# MiP_ProMini_16MHz-Pack.net
KiCad netlist of a schematic drawn in EAGLE
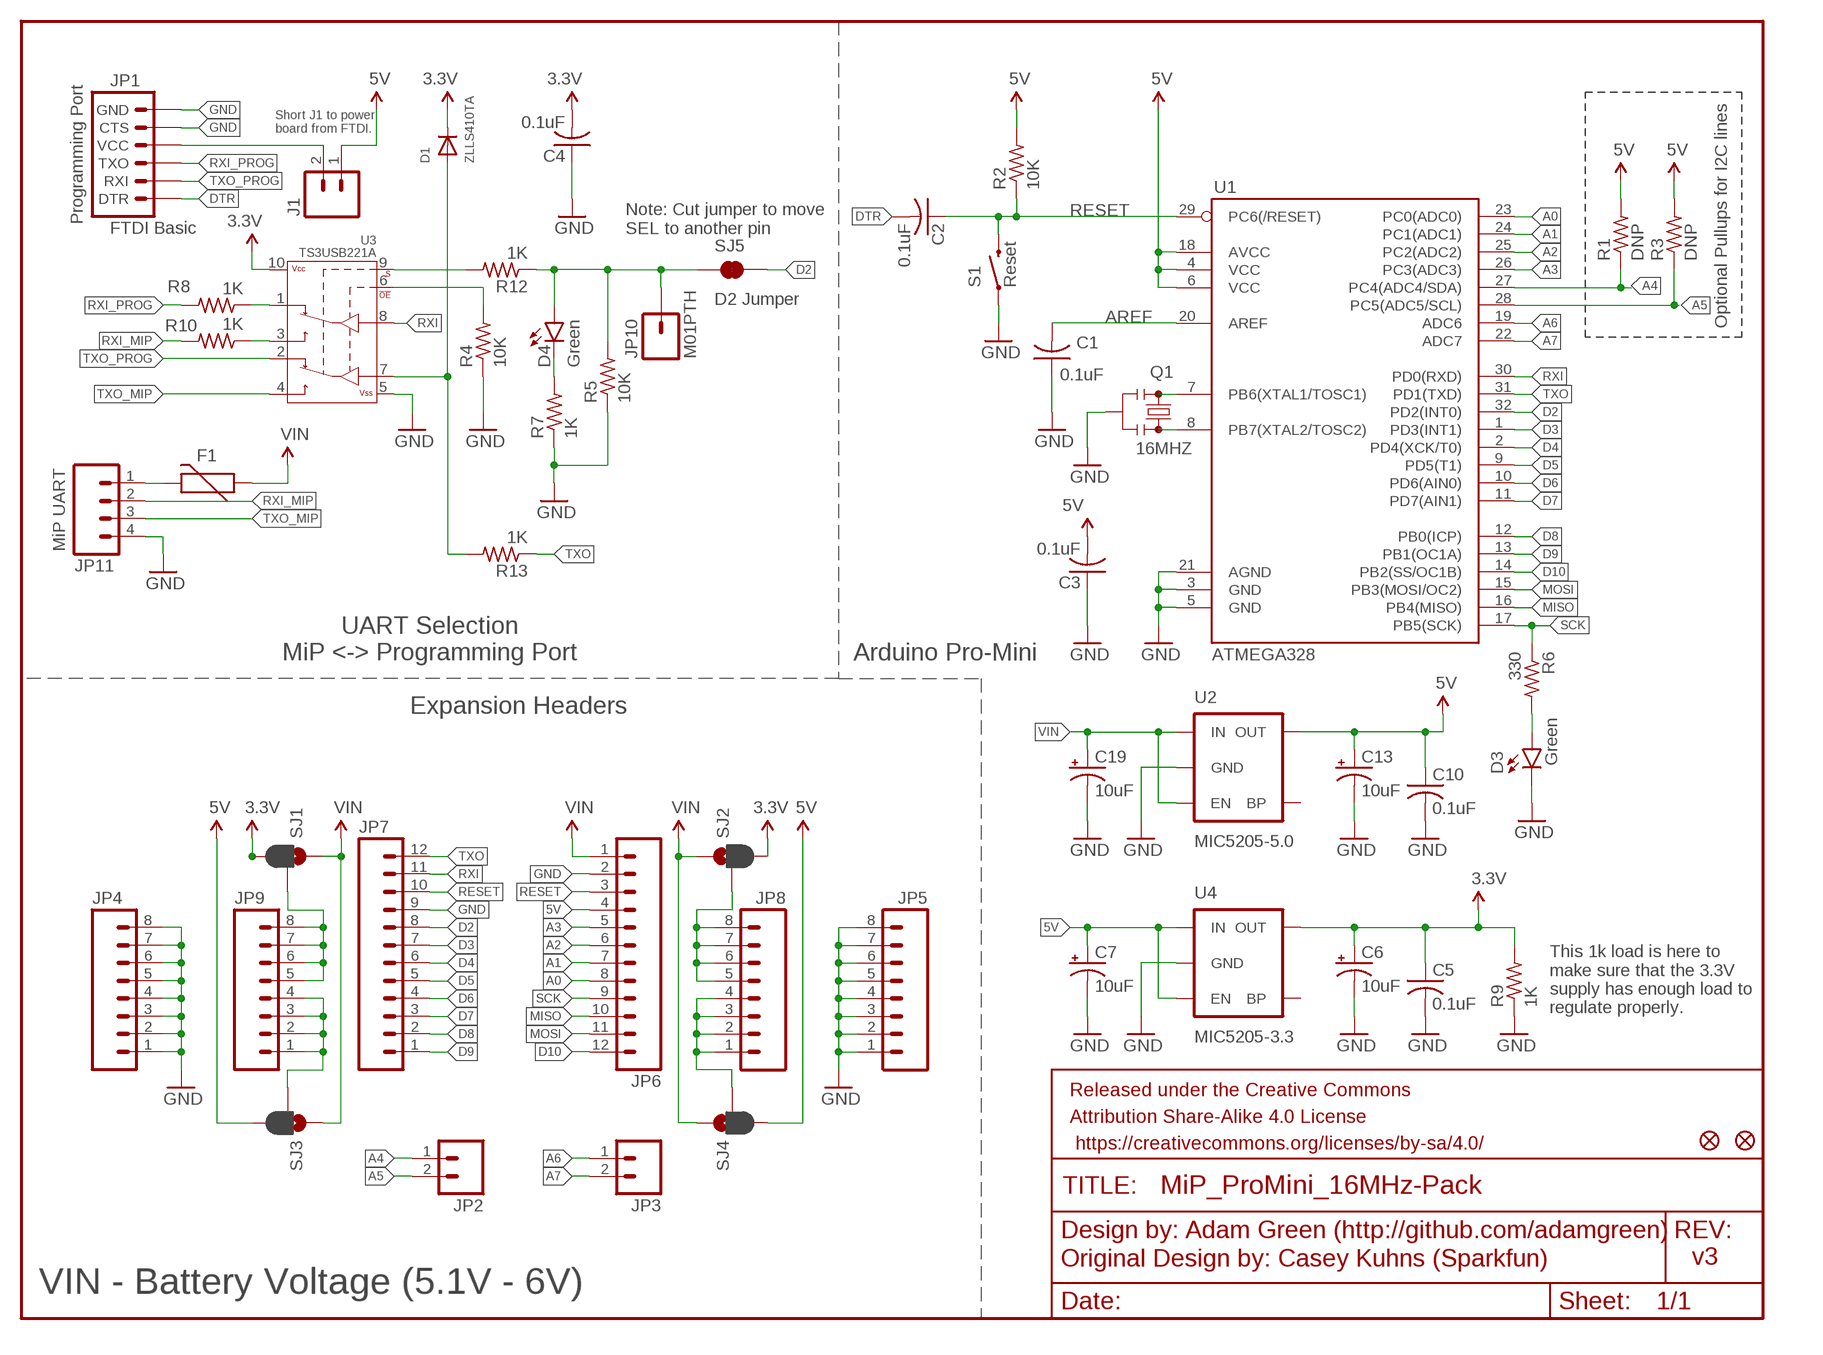
[diagram p0: schematic, sheet 1]

(export (version "E")
  (design (tool "Eeschema 10.0.6"))
  (components
    (comp (ref "C1")
      (value "0.1uF")
      (footprint "eagle-import:C0805")
      (libsource (lib "eagle-import") (part "C-USC0805"))
    )
    (comp (ref "C2")
      (value "0.1uF")
      (footprint "eagle-import:C0805")
      (libsource (lib "eagle-import") (part "C-USC0805"))
    )
    (comp (ref "C3")
      (value "0.1uF")
      (footprint "eagle-import:C0805")
      (libsource (lib "eagle-import") (part "C-USC0805"))
    )
    (comp (ref "C4")
      (value "0.1uF")
      (footprint "eagle-import:C0805")
      (libsource (lib "eagle-import") (part "C-USC0805"))
    )
    (comp (ref "C5")
      (value "0.1uF")
      (footprint "eagle-import:C0805")
      (libsource (lib "eagle-import") (part "C-USC0805"))
    )
    (comp (ref "C6")
      (value "10uF")
      (footprint "eagle-import:EIA3216")
      (libsource (lib "eagle-import") (part "CAP_POL1206"))
    )
    (comp (ref "C7")
      (value "10uF")
      (footprint "eagle-import:EIA3216")
      (libsource (lib "eagle-import") (part "CAP_POL1206"))
    )
    (comp (ref "C10")
      (value "0.1uF")
      (footprint "eagle-import:C0805")
      (libsource (lib "eagle-import") (part "C-USC0805"))
    )
    (comp (ref "C13")
      (value "10uF")
      (footprint "eagle-import:EIA3216")
      (libsource (lib "eagle-import") (part "CAP_POL1206"))
    )
    (comp (ref "C19")
      (value "10uF")
      (footprint "eagle-import:EIA3216")
      (libsource (lib "eagle-import") (part "CAP_POL1206"))
    )
    (comp (ref "D1")
      (value "ZLLS410TA")
      (footprint "eagle-import:SOD-323F")
      (libsource (lib "eagle-import") (part "DIODESOD-323F"))
    )
    (comp (ref "D3")
      (value "Green")
      (footprint "eagle-import:LED-0603")
      (libsource (lib "eagle-import") (part "LED-GREEN0603"))
    )
    (comp (ref "D4")
      (value "Green")
      (footprint "eagle-import:LED-0603")
      (libsource (lib "eagle-import") (part "LED-GREEN0603"))
    )
    (comp (ref "F1")
      (value "PTCCUSTOM")
      (footprint "eagle-import:PTC-1206-CUSTOM")
      (libsource (lib "eagle-import") (part "PTCCUSTOM"))
    )
    (comp (ref "FID1")
      (value "FIDUCIAL1X2")
      (footprint "eagle-import:FIDUCIAL-1X2")
      (libsource (lib "eagle-import") (part "FIDUCIAL1X2"))
    )
    (comp (ref "FID2")
      (value "FIDUCIAL1X2")
      (footprint "eagle-import:FIDUCIAL-1X2")
      (libsource (lib "eagle-import") (part "FIDUCIAL1X2"))
    )
    (comp (ref "FRAME1")
      (value "FRAME-LETTER")
      (footprint "eagle-import:CREATIVE_COMMONS")
      (libsource (lib "eagle-import") (part "FRAME-LETTER"))
    )
    (comp (ref "J1")
      (value "M02PTH")
      (footprint "eagle-import:1X02")
      (libsource (lib "eagle-import") (part "SparkFun-Connectors_M02PTH"))
    )
    (comp (ref "JP1")
      (value "FTDI Basic")
      (footprint "eagle-import:1X06")
      (libsource (lib "eagle-import") (part "ARDUINO_SERIAL_PROGRAMPTH"))
    )
    (comp (ref "JP2")
      (value "M02PTH")
      (footprint "eagle-import:1X02")
      (libsource (lib "eagle-import") (part "M02PTH"))
    )
    (comp (ref "JP3")
      (value "M02PTH")
      (footprint "eagle-import:1X02")
      (libsource (lib "eagle-import") (part "M02PTH"))
    )
    (comp (ref "JP4")
      (value "M081X08")
      (footprint "eagle-import:1X08")
      (libsource (lib "eagle-import") (part "M081X08"))
    )
    (comp (ref "JP5")
      (value "M081X08")
      (footprint "eagle-import:1X08")
      (libsource (lib "eagle-import") (part "M081X08"))
    )
    (comp (ref "JP6")
      (value "M12PTH")
      (footprint "eagle-import:1X12")
      (libsource (lib "eagle-import") (part "M12PTH"))
    )
    (comp (ref "JP7")
      (value "M12PTH")
      (footprint "eagle-import:1X12")
      (libsource (lib "eagle-import") (part "M12PTH"))
    )
    (comp (ref "JP8")
      (value "M081X08")
      (footprint "eagle-import:1X08")
      (libsource (lib "eagle-import") (part "M081X08"))
    )
    (comp (ref "JP9")
      (value "M081X08")
      (footprint "eagle-import:1X08")
      (libsource (lib "eagle-import") (part "M081X08"))
    )
    (comp (ref "JP10")
      (value "M01PTH")
      (footprint "eagle-import:1X01")
      (libsource (lib "eagle-import") (part "M01PTH"))
    )
    (comp (ref "JP11")
      (value "M04JST")
      (footprint "eagle-import:1X04-1.5MM_JST")
      (libsource (lib "eagle-import") (part "M04JST"))
    )
    (comp (ref "Q1")
      (value "16MHZ")
      (footprint "eagle-import:RESONATOR-SMD-CUSTOM")
      (libsource (lib "eagle-import") (part "RESONATORMURATA_16MHZ"))
    )
    (comp (ref "R1")
      (value "DNP")
      (footprint "eagle-import:R0805")
      (libsource (lib "eagle-import") (part "R-US_R0805"))
    )
    (comp (ref "R2")
      (value "10K")
      (footprint "eagle-import:R0805")
      (libsource (lib "eagle-import") (part "R-US_R0805"))
    )
    (comp (ref "R3")
      (value "DNP")
      (footprint "eagle-import:R0805")
      (libsource (lib "eagle-import") (part "R-US_R0805"))
    )
    (comp (ref "R4")
      (value "10K")
      (footprint "eagle-import:R0805")
      (libsource (lib "eagle-import") (part "R-US_R0805"))
    )
    (comp (ref "R5")
      (value "10K")
      (footprint "eagle-import:R0805")
      (libsource (lib "eagle-import") (part "R-US_R0805"))
    )
    (comp (ref "R6")
      (value "330")
      (footprint "eagle-import:R0805")
      (libsource (lib "eagle-import") (part "R-US_R0805"))
    )
    (comp (ref "R7")
      (value "1K")
      (footprint "eagle-import:R0805")
      (libsource (lib "eagle-import") (part "R-US_R0805"))
    )
    (comp (ref "R8")
      (value "1K")
      (footprint "eagle-import:R0805")
      (libsource (lib "eagle-import") (part "R-US_R0805"))
    )
    (comp (ref "R9")
      (value "1K")
      (footprint "eagle-import:R0805")
      (libsource (lib "eagle-import") (part "R-US_R0805"))
    )
    (comp (ref "R10")
      (value "1K")
      (footprint "eagle-import:R0805")
      (libsource (lib "eagle-import") (part "R-US_R0805"))
    )
    (comp (ref "R12")
      (value "1K")
      (footprint "eagle-import:R0805")
      (libsource (lib "eagle-import") (part "R-US_R0805"))
    )
    (comp (ref "R13")
      (value "1K")
      (footprint "eagle-import:R0805")
      (libsource (lib "eagle-import") (part "R-US_R0805"))
    )
    (comp (ref "S1")
      (value "Reset")
      (footprint "eagle-import:TACTILE-SWITCH-SMD-CKN9112CT-ND")
      (libsource (lib "eagle-import") (part "SWITCH-MOMENTARY-NOSMD"))
    )
    (comp (ref "SJ1")
      (value "JUMPER-PAD-3-2OF3_NC_BY_PASTE")
      (footprint "eagle-import:PAD-JUMPER-3-2OF3_NC_BY_PASTE_YES_SILK_FULL_BOX")
      (libsource (lib "eagle-import") (part "JUMPER-PAD-3-2OF3_NC_BY_PASTE"))
    )
    (comp (ref "SJ2")
      (value "JUMPER-PAD-3-2OF3_NC_BY_PASTE")
      (footprint "eagle-import:PAD-JUMPER-3-2OF3_NC_BY_PASTE_YES_SILK_FULL_BOX")
      (libsource (lib "eagle-import") (part "JUMPER-PAD-3-2OF3_NC_BY_PASTE"))
    )
    (comp (ref "SJ3")
      (value "JUMPER-PAD-3-2OF3_NC_BY_PASTE")
      (footprint "eagle-import:PAD-JUMPER-3-2OF3_NC_BY_PASTE_YES_SILK_FULL_BOX")
      (libsource (lib "eagle-import") (part "JUMPER-PAD-3-2OF3_NC_BY_PASTE"))
    )
    (comp (ref "SJ4")
      (value "JUMPER-PAD-3-2OF3_NC_BY_PASTE")
      (footprint "eagle-import:PAD-JUMPER-3-2OF3_NC_BY_PASTE_YES_SILK_FULL_BOX")
      (libsource (lib "eagle-import") (part "JUMPER-PAD-3-2OF3_NC_BY_PASTE"))
    )
    (comp (ref "SJ5")
      (value "D2 Jumper")
      (footprint "eagle-import:PAD-JUMPER-2-NC_BY_TRACE_YES_SILK")
      (libsource (lib "eagle-import") (part "JUMPER-PAD-2-NC_BY_TRACE"))
    )
    (comp (ref "U1")
      (value "ATMEGA328")
      (footprint "eagle-import:TQFP32-08")
      (libsource (lib "eagle-import") (part "ATMEGA328_SMT"))
    )
    (comp (ref "U2")
      (value "MIC5205-5.0")
      (footprint "eagle-import:SOT23-5")
      (libsource (lib "eagle-import") (part "MIC52053.3V"))
    )
    (comp (ref "U3")
      (value "TS3USB221A")
      (footprint "eagle-import:QFN-10-RSE-CUSTOM")
      (libsource (lib "eagle-import") (part "TS3USB221ACUSTOM"))
    )
    (comp (ref "U4")
      (value "MIC5205-3.3")
      (footprint "eagle-import:SOT23-5")
      (libsource (lib "eagle-import") (part "MIC52053.3V"))
    )
  )
  (nets
    (net (code "1") (name "/AREF") (class "Default")
      (node (ref "C1") (pin "2") (pinfunction "2_2") (pintype "passive"))
      (node (ref "U1") (pin "20") (pinfunction "AREF_20") (pintype "bidirectional"))
    )
    (net (code "2") (name "3.3V") (class "Default")
      (node (ref "C4") (pin "2") (pinfunction "2_2") (pintype "passive"))
      (node (ref "C5") (pin "1") (pinfunction "1_1") (pintype "passive"))
      (node (ref "C6") (pin "A") (pinfunction "+_A") (pintype "passive"))
      (node (ref "D1") (pin "C") (pinfunction "C_C") (pintype "passive"))
      (node (ref "R9") (pin "2") (pinfunction "2_2") (pintype "passive"))
      (node (ref "SJ1") (pin "3") (pinfunction "3_3") (pintype "passive"))
      (node (ref "SJ2") (pin "3") (pinfunction "3_3") (pintype "passive"))
      (node (ref "U3") (pin "10") (pinfunction "VCC_10") (pintype "bidirectional"))
      (node (ref "U4") (pin "5") (pinfunction "OUT_5") (pintype "passive"))
    )
    (net (code "3") (name "5V") (class "Default")
      (node (ref "C10") (pin "1") (pinfunction "1_1") (pintype "passive"))
      (node (ref "C13") (pin "A") (pinfunction "+_A") (pintype "passive"))
      (node (ref "C3") (pin "2") (pinfunction "2_2") (pintype "passive"))
      (node (ref "C7") (pin "A") (pinfunction "+_A") (pintype "passive"))
      (node (ref "J1") (pin "1") (pinfunction "1_1") (pintype "passive"))
      (node (ref "JP6") (pin "4") (pinfunction "4_4") (pintype "passive"))
      (node (ref "R1") (pin "2") (pinfunction "2_2") (pintype "passive"))
      (node (ref "R2") (pin "2") (pinfunction "2_2") (pintype "passive"))
      (node (ref "R3") (pin "2") (pinfunction "2_2") (pintype "passive"))
      (node (ref "SJ3") (pin "3") (pinfunction "3_3") (pintype "passive"))
      (node (ref "SJ4") (pin "3") (pinfunction "3_3") (pintype "passive"))
      (node (ref "U1") (pin "18") (pinfunction "AVCC_18") (pintype "bidirectional"))
      (node (ref "U1") (pin "4") (pinfunction "VCC_4") (pintype "bidirectional"))
      (node (ref "U1") (pin "6") (pinfunction "VCC_6") (pintype "bidirectional"))
      (node (ref "U2") (pin "5") (pinfunction "OUT_5") (pintype "passive"))
      (node (ref "U4") (pin "1") (pinfunction "IN_1") (pintype "input"))
      (node (ref "U4") (pin "3") (pinfunction "EN_3") (pintype "input"))
    )
    (net (code "4") (name "A0") (class "Default")
      (node (ref "JP6") (pin "8") (pinfunction "8_8") (pintype "passive"))
      (node (ref "U1") (pin "23") (pinfunction "PC0(ADC0)_23") (pintype "bidirectional"))
    )
    (net (code "5") (name "A1") (class "Default")
      (node (ref "JP6") (pin "7") (pinfunction "7_7") (pintype "passive"))
      (node (ref "U1") (pin "24") (pinfunction "PC1(ADC1)_24") (pintype "bidirectional"))
    )
    (net (code "6") (name "A2") (class "Default")
      (node (ref "JP6") (pin "6") (pinfunction "6_6") (pintype "passive"))
      (node (ref "U1") (pin "25") (pinfunction "PC2(ADC2)_25") (pintype "bidirectional"))
    )
    (net (code "7") (name "A3") (class "Default")
      (node (ref "JP6") (pin "5") (pinfunction "5_5") (pintype "passive"))
      (node (ref "U1") (pin "26") (pinfunction "PC3(ADC3)_26") (pintype "bidirectional"))
    )
    (net (code "8") (name "A4") (class "Default")
      (node (ref "JP2") (pin "1") (pinfunction "1_1") (pintype "passive"))
      (node (ref "R1") (pin "1") (pinfunction "1_1") (pintype "passive"))
      (node (ref "U1") (pin "27") (pinfunction "PC4(ADC4/SDA)_27") (pintype "bidirectional"))
    )
    (net (code "9") (name "A5") (class "Default")
      (node (ref "JP2") (pin "2") (pinfunction "2_2") (pintype "passive"))
      (node (ref "R3") (pin "1") (pinfunction "1_1") (pintype "passive"))
      (node (ref "U1") (pin "28") (pinfunction "PC5(ADC5/SCL)_28") (pintype "bidirectional"))
    )
    (net (code "10") (name "A6") (class "Default")
      (node (ref "JP3") (pin "1") (pinfunction "1_1") (pintype "passive"))
      (node (ref "U1") (pin "19") (pinfunction "ADC6_19") (pintype "bidirectional"))
    )
    (net (code "11") (name "A7") (class "Default")
      (node (ref "JP3") (pin "2") (pinfunction "2_2") (pintype "passive"))
      (node (ref "U1") (pin "22") (pinfunction "ADC7_22") (pintype "bidirectional"))
    )
    (net (code "12") (name "D2") (class "Default")
      (node (ref "JP7") (pin "8") (pinfunction "8_8") (pintype "passive"))
      (node (ref "SJ5") (pin "2") (pinfunction "2_2") (pintype "passive"))
      (node (ref "U1") (pin "32") (pinfunction "PD2(INT0)_32") (pintype "bidirectional"))
    )
    (net (code "13") (name "D3") (class "Default")
      (node (ref "JP7") (pin "7") (pinfunction "7_7") (pintype "passive"))
      (node (ref "U1") (pin "1") (pinfunction "PD3(INT1)_1") (pintype "bidirectional"))
    )
    (net (code "14") (name "D4") (class "Default")
      (node (ref "JP7") (pin "6") (pinfunction "6_6") (pintype "passive"))
      (node (ref "U1") (pin "2") (pinfunction "PD4(XCK/T0)_2") (pintype "bidirectional"))
    )
    (net (code "15") (name "D5") (class "Default")
      (node (ref "JP7") (pin "5") (pinfunction "5_5") (pintype "passive"))
      (node (ref "U1") (pin "9") (pinfunction "PD5(T1)_9") (pintype "bidirectional"))
    )
    (net (code "16") (name "D6") (class "Default")
      (node (ref "JP7") (pin "4") (pinfunction "4_4") (pintype "passive"))
      (node (ref "U1") (pin "10") (pinfunction "PD6(AIN0)_10") (pintype "bidirectional"))
    )
    (net (code "17") (name "D7") (class "Default")
      (node (ref "JP7") (pin "3") (pinfunction "3_3") (pintype "passive"))
      (node (ref "U1") (pin "11") (pinfunction "PD7(AIN1)_11") (pintype "bidirectional"))
    )
    (net (code "18") (name "D8") (class "Default")
      (node (ref "JP7") (pin "2") (pinfunction "2_2") (pintype "passive"))
      (node (ref "U1") (pin "12") (pinfunction "PB0(ICP)_12") (pintype "bidirectional"))
    )
    (net (code "19") (name "D9") (class "Default")
      (node (ref "JP7") (pin "1") (pinfunction "1_1") (pintype "passive"))
      (node (ref "U1") (pin "13") (pinfunction "PB1(OC1A)_13") (pintype "bidirectional"))
    )
    (net (code "20") (name "D10") (class "Default")
      (node (ref "JP6") (pin "12") (pinfunction "12_12") (pintype "passive"))
      (node (ref "U1") (pin "14") (pinfunction "PB2(SS/OC1B)_14") (pintype "bidirectional"))
    )
    (net (code "21") (name "DTR") (class "Default")
      (node (ref "C2") (pin "2") (pinfunction "2_2") (pintype "passive"))
      (node (ref "JP1") (pin "1") (pinfunction "DTR_1") (pintype "passive"))
    )
    (net (code "22") (name "GND") (class "Default")
      (node (ref "C1") (pin "1") (pinfunction "1_1") (pintype "passive"))
      (node (ref "C10") (pin "2") (pinfunction "2_2") (pintype "passive"))
      (node (ref "C13") (pin "C") (pinfunction "-_C") (pintype "passive"))
      (node (ref "C19") (pin "C") (pinfunction "-_C") (pintype "passive"))
      (node (ref "C3") (pin "1") (pinfunction "1_1") (pintype "passive"))
      (node (ref "C4") (pin "1") (pinfunction "1_1") (pintype "passive"))
      (node (ref "C5") (pin "2") (pinfunction "2_2") (pintype "passive"))
      (node (ref "C6") (pin "C") (pinfunction "-_C") (pintype "passive"))
      (node (ref "C7") (pin "C") (pinfunction "-_C") (pintype "passive"))
      (node (ref "D3") (pin "C") (pinfunction "C_C") (pintype "passive"))
      (node (ref "JP1") (pin "5") (pinfunction "CTS_5") (pintype "passive"))
      (node (ref "JP1") (pin "6") (pinfunction "GND_6") (pintype "passive"))
      (node (ref "JP11") (pin "4") (pinfunction "4_4") (pintype "passive"))
      (node (ref "JP4") (pin "1") (pinfunction "1_1") (pintype "passive"))
      (node (ref "JP4") (pin "2") (pinfunction "2_2") (pintype "passive"))
      (node (ref "JP4") (pin "3") (pinfunction "3_3") (pintype "passive"))
      (node (ref "JP4") (pin "4") (pinfunction "4_4") (pintype "passive"))
      (node (ref "JP4") (pin "5") (pinfunction "5_5") (pintype "passive"))
      (node (ref "JP4") (pin "6") (pinfunction "6_6") (pintype "passive"))
      (node (ref "JP4") (pin "7") (pinfunction "7_7") (pintype "passive"))
      (node (ref "JP4") (pin "8") (pinfunction "8_8") (pintype "passive"))
      (node (ref "JP5") (pin "1") (pinfunction "1_1") (pintype "passive"))
      (node (ref "JP5") (pin "2") (pinfunction "2_2") (pintype "passive"))
      (node (ref "JP5") (pin "3") (pinfunction "3_3") (pintype "passive"))
      (node (ref "JP5") (pin "4") (pinfunction "4_4") (pintype "passive"))
      (node (ref "JP5") (pin "5") (pinfunction "5_5") (pintype "passive"))
      (node (ref "JP5") (pin "6") (pinfunction "6_6") (pintype "passive"))
      (node (ref "JP5") (pin "7") (pinfunction "7_7") (pintype "passive"))
      (node (ref "JP5") (pin "8") (pinfunction "8_8") (pintype "passive"))
      (node (ref "JP6") (pin "2") (pinfunction "2_2") (pintype "passive"))
      (node (ref "JP7") (pin "9") (pinfunction "9_9") (pintype "passive"))
      (node (ref "Q1") (pin "2") (pinfunction "2_2") (pintype "passive"))
      (node (ref "R4") (pin "1") (pinfunction "1_1") (pintype "passive"))
      (node (ref "R5") (pin "1") (pinfunction "1_1") (pintype "passive"))
      (node (ref "R7") (pin "1") (pinfunction "1_1") (pintype "passive"))
      (node (ref "R9") (pin "1") (pinfunction "1_1") (pintype "passive"))
      (node (ref "S1") (pin "1") (pinfunction "1_1") (pintype "passive"))
      (node (ref "U1") (pin "21") (pinfunction "AGND_21") (pintype "bidirectional"))
      (node (ref "U1") (pin "3") (pinfunction "GND_3") (pintype "bidirectional"))
      (node (ref "U1") (pin "5") (pinfunction "GND_5") (pintype "bidirectional"))
      (node (ref "U2") (pin "2") (pinfunction "GND_2") (pintype "input"))
      (node (ref "U3") (pin "5") (pinfunction "VSS_5") (pintype "bidirectional"))
      (node (ref "U4") (pin "2") (pinfunction "GND_2") (pintype "input"))
    )
    (net (code "23") (name "MISO") (class "Default")
      (node (ref "JP6") (pin "10") (pinfunction "10_10") (pintype "passive"))
      (node (ref "U1") (pin "16") (pinfunction "PB4(MISO)_16") (pintype "bidirectional"))
    )
    (net (code "24") (name "MOSI") (class "Default")
      (node (ref "JP6") (pin "11") (pinfunction "11_11") (pintype "passive"))
      (node (ref "U1") (pin "15") (pinfunction "PB3(MOSI/OC2)_15") (pintype "bidirectional"))
    )
    (net (code "25") (name "Net-(D3-PadA)") (class "Default")
      (node (ref "D3") (pin "A") (pinfunction "A_A") (pintype "passive"))
      (node (ref "R6") (pin "2") (pinfunction "2_2") (pintype "passive"))
    )
    (net (code "26") (name "Net-(D4-PadA)") (class "Default")
      (node (ref "D4") (pin "A") (pinfunction "A_A") (pintype "passive"))
      (node (ref "JP10") (pin "1") (pinfunction "1_1") (pintype "passive"))
      (node (ref "R12") (pin "1") (pinfunction "1_1") (pintype "passive"))
      (node (ref "R5") (pin "2") (pinfunction "2_2") (pintype "passive"))
      (node (ref "SJ5") (pin "1") (pinfunction "1_1") (pintype "passive"))
    )
    (net (code "27") (name "Net-(D4-PadC)") (class "Default")
      (node (ref "D4") (pin "C") (pinfunction "C_C") (pintype "passive"))
      (node (ref "R7") (pin "2") (pinfunction "2_2") (pintype "passive"))
    )
    (net (code "28") (name "Net-(F1-Pad2)") (class "Default")
      (node (ref "F1") (pin "2") (pinfunction "2_2") (pintype "bidirectional"))
      (node (ref "JP11") (pin "1") (pinfunction "1_1") (pintype "passive"))
    )
    (net (code "29") (name "Net-(JP1-VCC)") (class "Default")
      (node (ref "J1") (pin "2") (pinfunction "2_2") (pintype "passive"))
      (node (ref "JP1") (pin "4") (pinfunction "VCC_4") (pintype "passive"))
    )
    (net (code "30") (name "Net-(JP8-Pad1)") (class "Default")
      (node (ref "JP8") (pin "1") (pinfunction "1_1") (pintype "passive"))
      (node (ref "JP8") (pin "2") (pinfunction "2_2") (pintype "passive"))
      (node (ref "JP8") (pin "3") (pinfunction "3_3") (pintype "passive"))
      (node (ref "JP8") (pin "4") (pinfunction "4_4") (pintype "passive"))
      (node (ref "SJ4") (pin "2") (pinfunction "2_2") (pintype "passive"))
    )
    (net (code "31") (name "Net-(JP8-Pad5)") (class "Default")
      (node (ref "JP8") (pin "5") (pinfunction "5_5") (pintype "passive"))
      (node (ref "JP8") (pin "6") (pinfunction "6_6") (pintype "passive"))
      (node (ref "JP8") (pin "7") (pinfunction "7_7") (pintype "passive"))
      (node (ref "JP8") (pin "8") (pinfunction "8_8") (pintype "passive"))
      (node (ref "SJ2") (pin "2") (pinfunction "2_2") (pintype "passive"))
    )
    (net (code "32") (name "Net-(JP9-Pad1)") (class "Default")
      (node (ref "JP9") (pin "1") (pinfunction "1_1") (pintype "passive"))
      (node (ref "JP9") (pin "2") (pinfunction "2_2") (pintype "passive"))
      (node (ref "JP9") (pin "3") (pinfunction "3_3") (pintype "passive"))
      (node (ref "JP9") (pin "4") (pinfunction "4_4") (pintype "passive"))
      (node (ref "SJ3") (pin "2") (pinfunction "2_2") (pintype "passive"))
    )
    (net (code "33") (name "Net-(JP9-Pad5)") (class "Default")
      (node (ref "JP9") (pin "5") (pinfunction "5_5") (pintype "passive"))
      (node (ref "JP9") (pin "6") (pinfunction "6_6") (pintype "passive"))
      (node (ref "JP9") (pin "7") (pinfunction "7_7") (pintype "passive"))
      (node (ref "JP9") (pin "8") (pinfunction "8_8") (pintype "passive"))
      (node (ref "SJ1") (pin "2") (pinfunction "2_2") (pintype "passive"))
    )
    (net (code "34") (name "Net-(U1-PB6(XTAL1{slash}TOSC1))") (class "Default")
      (node (ref "Q1") (pin "1") (pinfunction "1_1") (pintype "passive"))
      (node (ref "U1") (pin "7") (pinfunction "PB6(XTAL1/TOSC1)_7") (pintype "bidirectional"))
    )
    (net (code "35") (name "Net-(U1-PB7(XTAL2{slash}TOSC2))") (class "Default")
      (node (ref "Q1") (pin "3") (pinfunction "3_3") (pintype "passive"))
      (node (ref "U1") (pin "8") (pinfunction "PB7(XTAL2/TOSC2)_8") (pintype "bidirectional"))
    )
    (net (code "36") (name "Net-(U3-1D+)") (class "Default")
      (node (ref "R8") (pin "1") (pinfunction "1_1") (pintype "passive"))
      (node (ref "U3") (pin "1") (pinfunction "1D+_1") (pintype "bidirectional"))
    )
    (net (code "37") (name "Net-(U3-2D+)") (class "Default")
      (node (ref "R10") (pin "1") (pinfunction "1_1") (pintype "passive"))
      (node (ref "U3") (pin "3") (pinfunction "2D+_3") (pintype "bidirectional"))
    )
    (net (code "38") (name "Net-(U3-D-)") (class "Default")
      (node (ref "D1") (pin "A") (pinfunction "A_A") (pintype "passive"))
      (node (ref "R13") (pin "2") (pinfunction "2_2") (pintype "passive"))
      (node (ref "U3") (pin "7") (pinfunction "D-_7") (pintype "bidirectional"))
    )
    (net (code "39") (name "Net-(U3-S)") (class "Default")
      (node (ref "R12") (pin "2") (pinfunction "2_2") (pintype "passive"))
      (node (ref "U3") (pin "9") (pinfunction "S_9") (pintype "bidirectional"))
    )
    (net (code "40") (name "Net-(U3-~{OE})") (class "Default")
      (node (ref "R4") (pin "2") (pinfunction "2_2") (pintype "passive"))
      (node (ref "U3") (pin "6") (pinfunction "~{OE}_6") (pintype "bidirectional"))
    )
    (net (code "41") (name "RESET") (class "Default")
      (node (ref "C2") (pin "1") (pinfunction "1_1") (pintype "passive"))
      (node (ref "JP6") (pin "3") (pinfunction "3_3") (pintype "passive"))
      (node (ref "JP7") (pin "10") (pinfunction "10_10") (pintype "passive"))
      (node (ref "R2") (pin "1") (pinfunction "1_1") (pintype "passive"))
      (node (ref "S1") (pin "3") (pinfunction "2_3") (pintype "passive"))
      (node (ref "U1") (pin "29") (pinfunction "PC6(/RESET)_29") (pintype "bidirectional"))
    )
    (net (code "42") (name "RXI") (class "Default")
      (node (ref "JP7") (pin "11") (pinfunction "11_11") (pintype "passive"))
      (node (ref "U1") (pin "30") (pinfunction "PD0(RXD)_30") (pintype "bidirectional"))
      (node (ref "U3") (pin "8") (pinfunction "D+_8") (pintype "bidirectional"))
    )
    (net (code "43") (name "RXI_MIP") (class "Default")
      (node (ref "JP11") (pin "2") (pinfunction "2_2") (pintype "passive"))
      (node (ref "R10") (pin "2") (pinfunction "2_2") (pintype "passive"))
    )
    (net (code "44") (name "RXI_PROG") (class "Default")
      (node (ref "JP1") (pin "3") (pinfunction "TXO_3") (pintype "passive"))
      (node (ref "R8") (pin "2") (pinfunction "2_2") (pintype "passive"))
    )
    (net (code "45") (name "SCK") (class "Default")
      (node (ref "JP6") (pin "9") (pinfunction "9_9") (pintype "passive"))
      (node (ref "R6") (pin "1") (pinfunction "1_1") (pintype "passive"))
      (node (ref "U1") (pin "17") (pinfunction "PB5(SCK)_17") (pintype "bidirectional"))
    )
    (net (code "46") (name "TXO") (class "Default")
      (node (ref "JP7") (pin "12") (pinfunction "12_12") (pintype "passive"))
      (node (ref "R13") (pin "1") (pinfunction "1_1") (pintype "passive"))
      (node (ref "U1") (pin "31") (pinfunction "PD1(TXD)_31") (pintype "bidirectional"))
    )
    (net (code "47") (name "TXO_MIP") (class "Default")
      (node (ref "JP11") (pin "3") (pinfunction "3_3") (pintype "passive"))
      (node (ref "U3") (pin "4") (pinfunction "2D-_4") (pintype "bidirectional"))
    )
    (net (code "48") (name "TXO_PROG") (class "Default")
      (node (ref "JP1") (pin "2") (pinfunction "RXI_2") (pintype "passive"))
      (node (ref "U3") (pin "2") (pinfunction "1D-_2") (pintype "bidirectional"))
    )
    (net (code "49") (name "VIN") (class "Default")
      (node (ref "C19") (pin "A") (pinfunction "+_A") (pintype "passive"))
      (node (ref "F1") (pin "1") (pinfunction "1_1") (pintype "bidirectional"))
      (node (ref "JP6") (pin "1") (pinfunction "1_1") (pintype "passive"))
      (node (ref "SJ1") (pin "1") (pinfunction "1_1") (pintype "passive"))
      (node (ref "SJ2") (pin "1") (pinfunction "1_1") (pintype "passive"))
      (node (ref "SJ3") (pin "1") (pinfunction "1_1") (pintype "passive"))
      (node (ref "SJ4") (pin "1") (pinfunction "1_1") (pintype "passive"))
      (node (ref "U2") (pin "1") (pinfunction "IN_1") (pintype "input"))
      (node (ref "U2") (pin "3") (pinfunction "EN_3") (pintype "input"))
    )
    (net (code "50") (name "unconnected-(U2-BP-Pad4)") (class "Default")
      (node (ref "U2") (pin "4") (pinfunction "BP_4") (pintype "input"))
    )
    (net (code "51") (name "unconnected-(U4-BP-Pad4)") (class "Default")
      (node (ref "U4") (pin "4") (pinfunction "BP_4") (pintype "input"))
    )
  )
)
